# LeggedBot.net
KiCad netlist of a schematic drawn in Altium Designer
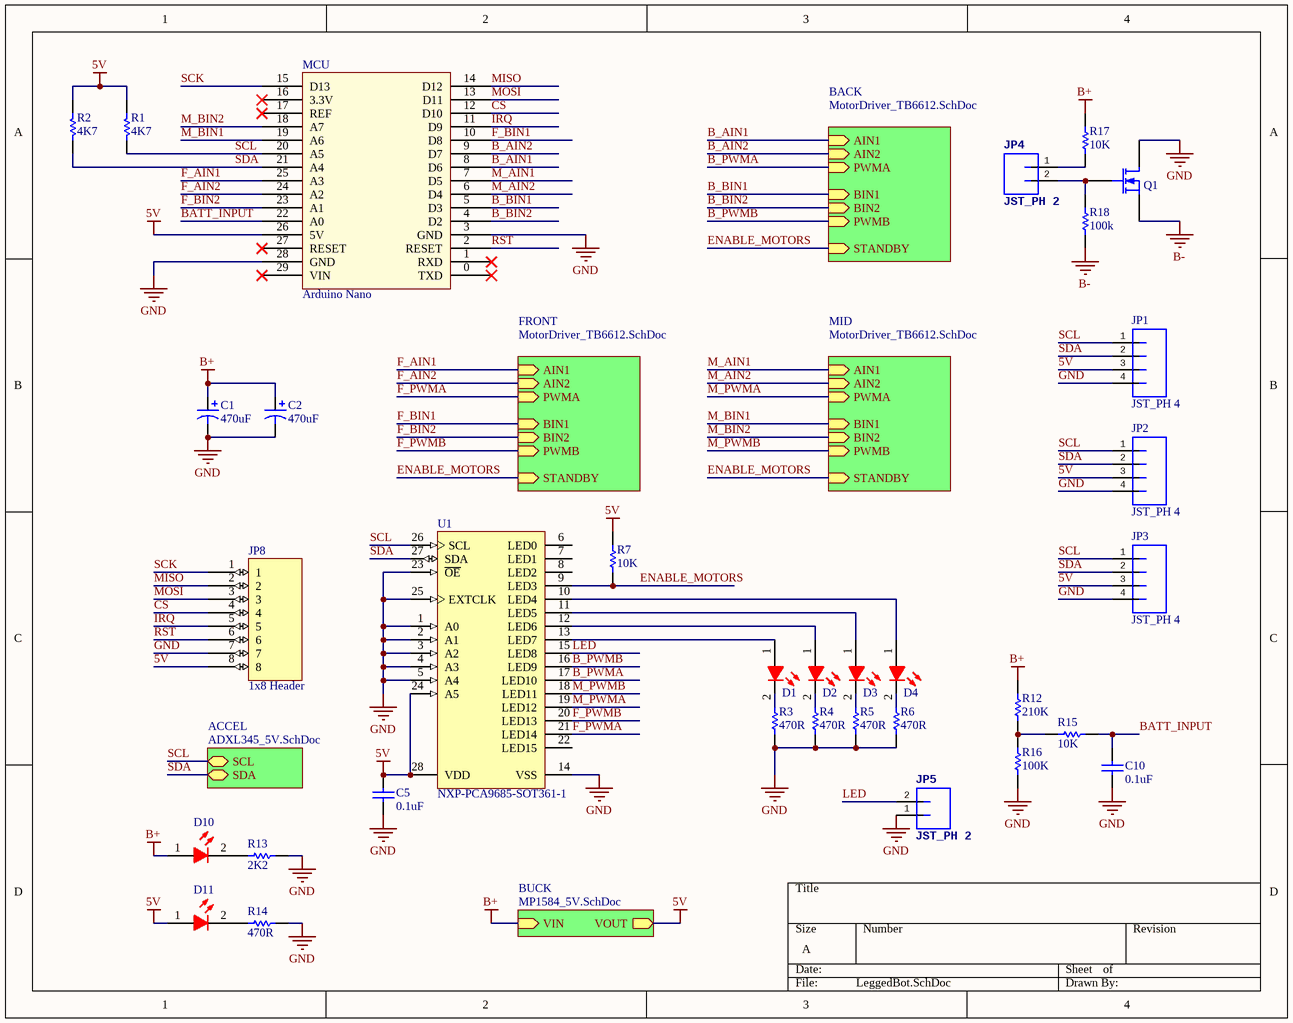
[diagram p0: LeggedBot.SchDoc]

(export (version "E")
  (design (tool "Eeschema 10.0.6"))
  (components
    (comp (ref "C1")
      (value "470uF")
      (footprint "CAP_10mm")
      (description "Generic electrolytic capacitor w/ 10mm diameter and 5mm pitch")
      (libsource (lib "Components") (part "CAP_10MM_GENERIC"))
    )
    (comp (ref "C2")
      (value "470uF")
      (footprint "CAP_10mm")
      (description "Generic electrolytic capacitor w/ 10mm diameter and 5mm pitch")
      (libsource (lib "Components") (part "CAP_10MM_GENERIC"))
    )
    (comp (ref "C5")
      (value "0.1uF")
      (footprint "CAPC0603(1608)100_L")
      (description "CAP 100nF 50V ±5% 0603 (1608 Metric) Thickness 1mm SMD")
      (fields (field (name "TOLERANCE") "Â±5%"))
      (libsource (lib "Altium Content Vault") (part "CMP-1035-02591-1"))
    )
    (comp (ref "C10")
      (value "0.1uF")
      (footprint "CAPC0603(1608)100_L")
      (description "CAP 100nF 50V ±5% 0603 (1608 Metric) Thickness 1mm SMD")
      (fields (field (name "TOLERANCE") "Â±5%"))
      (libsource (lib "Altium Content Vault") (part "CMP-1035-02591-1"))
    )
    (comp (ref "D1")
      (value "TLSU1008A(T04)")
      (footprint "TOSH-0603LED_RED_V")
      (description "LED, Red 0603 (1608) 63mCd")
      (fields (field (name "MANUFACTURER") "Toshiba"))
      (libsource (lib "Altium Content Vault") (part "CMP-0444-00001-1"))
    )
    (comp (ref "D2")
      (value "TLSU1008A(T04)")
      (footprint "TOSH-0603LED_RED_V")
      (description "LED, Red 0603 (1608) 63mCd")
      (fields (field (name "MANUFACTURER") "Toshiba"))
      (libsource (lib "Altium Content Vault") (part "CMP-0444-00001-1"))
    )
    (comp (ref "D3")
      (value "TLSU1008A(T04)")
      (footprint "TOSH-0603LED_RED_V")
      (description "LED, Red 0603 (1608) 63mCd")
      (fields (field (name "MANUFACTURER") "Toshiba"))
      (libsource (lib "Altium Content Vault") (part "CMP-0444-00001-1"))
    )
    (comp (ref "D4")
      (value "TLSU1008A(T04)")
      (footprint "TOSH-0603LED_RED_V")
      (description "LED, Red 0603 (1608) 63mCd")
      (fields (field (name "MANUFACTURER") "Toshiba"))
      (libsource (lib "Altium Content Vault") (part "CMP-0444-00001-1"))
    )
    (comp (ref "D10")
      (value "TLSU1008A(T04)")
      (footprint "TOSH-0603LED_RED_V")
      (description "LED, Red 0603 (1608) 63mCd")
      (fields (field (name "MANUFACTURER") "Toshiba"))
      (libsource (lib "Altium Content Vault") (part "CMP-0444-00001-1"))
    )
    (comp (ref "D11")
      (value "TLSU1008A(T04)")
      (footprint "TOSH-0603LED_RED_V")
      (description "LED, Red 0603 (1608) 63mCd")
      (fields (field (name "MANUFACTURER") "Toshiba"))
      (libsource (lib "Altium Content Vault") (part "CMP-0444-00001-1"))
    )
    (comp (ref "JP1")
      (value "JST_PH 4")
      (footprint "JST-4-PTH-VERT")
      (libsource (lib "Components") (part "JST_PH 4"))
    )
    (comp (ref "JP2")
      (value "JST_PH 4")
      (footprint "JST-4-PTH-VERT")
      (libsource (lib "Components") (part "JST_PH 4"))
    )
    (comp (ref "JP3")
      (value "JST_PH 4")
      (footprint "JST-4-PTH-VERT")
      (libsource (lib "Components") (part "JST_PH 4"))
    )
    (comp (ref "JP4")
      (value "JST_PH 2")
      (footprint "JST-2-PTH-VERT")
      (libsource (lib "Components") (part "JST_PH 2"))
    )
    (comp (ref "JP5")
      (value "JST_PH 2")
      (footprint "JST-2-PTH-VERT")
      (libsource (lib "Components") (part "JST_PH 2"))
    )
    (comp (ref "JP8")
      (value "1x8 Header")
      (footprint "Header 8x1 8.5mm")
      (libsource (lib "Components") (part "1x8 Header"))
    )
    (comp (ref "MCU")
      (value "Arduino Nano")
      (footprint "Arduino Nano")
      (libsource (lib "Components") (part "Arduino Nano"))
    )
    (comp (ref "Q1")
      (value "MOSFET-N")
      (footprint "SOIC127P600X175-8N")
      (description "N-Channel MOSFET")
      (fields (field (name "PUBLISHER") "Altium Limited"))
      (libsource (lib "Components") (part "MOSFET-N"))
    )
    (comp (ref "R1")
      (value "4K7")
      (footprint "RESC0603(1608)_L")
      (description "4K7 0.1W 5% 0603 (1608 Metric)  SMD")
      (fields (field (name "TOLERANCE") "5 %") (field (name "POWER") "0.1 W"))
      (libsource (lib "Altium Content Vault") (part "CMP-1012-00090-1"))
    )
    (comp (ref "R2")
      (value "4K7")
      (footprint "RESC0603(1608)_L")
      (description "4K7 0.1W 5% 0603 (1608 Metric)  SMD")
      (fields (field (name "TOLERANCE") "5 %") (field (name "POWER") "0.1 W"))
      (libsource (lib "Altium Content Vault") (part "CMP-1012-00090-1"))
    )
    (comp (ref "R3")
      (value "470R")
      (footprint "RESC0603(1608)_L")
      (description "470R 0.1W 5% 0603 (1608 Metric)  SMD")
      (fields (field (name "TOLERANCE") "5 %") (field (name "POWER") "0.1 W"))
      (libsource (lib "Altium Content Vault") (part "RES"))
    )
    (comp (ref "R4")
      (value "470R")
      (footprint "RESC0603(1608)_L")
      (description "470R 0.1W 5% 0603 (1608 Metric)  SMD")
      (fields (field (name "TOLERANCE") "5 %") (field (name "POWER") "0.1 W"))
      (libsource (lib "Altium Content Vault") (part "RES"))
    )
    (comp (ref "R5")
      (value "470R")
      (footprint "RESC0603(1608)_L")
      (description "470R 0.1W 5% 0603 (1608 Metric)  SMD")
      (fields (field (name "TOLERANCE") "5 %") (field (name "POWER") "0.1 W"))
      (libsource (lib "Altium Content Vault") (part "CMP-1012-00066-1"))
    )
    (comp (ref "R6")
      (value "470R")
      (footprint "RESC0603(1608)_L")
      (description "470R 0.1W 5% 0603 (1608 Metric)  SMD")
      (fields (field (name "TOLERANCE") "5 %") (field (name "POWER") "0.1 W"))
      (libsource (lib "Altium Content Vault") (part "CMP-1012-00066-1"))
    )
    (comp (ref "R7")
      (value "10K")
      (footprint "RESC0603(1608)_L")
      (description "10K 0.1W 5% 0603 (1608 Metric)  SMD")
      (fields (field (name "TOLERANCE") "5 %") (field (name "POWER") "0.1 W"))
      (libsource (lib "Altium Content Vault") (part "RES"))
    )
    (comp (ref "R12")
      (value "210K")
      (footprint "RESC0603(1608)_L")
      (description "210K 0.1W 1% 0603 (1608 Metric)  SMD")
      (fields (field (name "POWER") "0.1 W") (field (name "TOLERANCE") "1 %"))
      (libsource (lib "Altium Content Vault") (part "CMP-1012-00770-1"))
    )
    (comp (ref "R13")
      (value "2K2")
      (footprint "RESC0603(1608)_L")
      (description "2K2 0.1W 5% 0603 (1608 Metric)  SMD")
      (fields (field (name "POWER") "0.1 W") (field (name "TOLERANCE") "5 %"))
      (libsource (lib "Altium Content Vault") (part "RES"))
    )
    (comp (ref "R14")
      (value "470R")
      (footprint "RESC0603(1608)_L")
      (description "470R 0.1W 5% 0603 (1608 Metric)  SMD")
      (fields (field (name "TOLERANCE") "5 %") (field (name "POWER") "0.1 W"))
      (libsource (lib "Altium Content Vault") (part "RES"))
    )
    (comp (ref "R15")
      (value "10K")
      (footprint "RESC0603(1608)_L")
      (description "10K 0.1W 5% 0603 (1608 Metric)  SMD")
      (fields (field (name "TOLERANCE") "5 %") (field (name "POWER") "0.1 W"))
      (libsource (lib "Altium Content Vault") (part "CMP-1012-00098-1"))
    )
    (comp (ref "R16")
      (value "100K")
      (footprint "RESC0603(1608)_L")
      (description "100K 0.1W 1% 0603 (1608 Metric)  SMD")
      (fields (field (name "POWER") "0.1 W") (field (name "TOLERANCE") "1 %"))
      (libsource (lib "Altium Content Vault") (part "RES"))
    )
    (comp (ref "R17")
      (value "10K")
      (footprint "RESC0603(1608)_L")
      (description "10K 0.1W 5% 0603 (1608 Metric)  SMD")
      (fields (field (name "TOLERANCE") "5 %") (field (name "POWER") "0.1 W"))
      (libsource (lib "Altium Content Vault") (part "CMP-1012-00098-1"))
    )
    (comp (ref "R18")
      (value "100k")
      (footprint "RESC0603(1608)_L")
      (description "100K 0.1W 1% 0603 (1608 Metric)  SMD")
      (fields (field (name "POWER") "0.1 W") (field (name "TOLERANCE") "1 %"))
      (libsource (lib "Altium Content Vault") (part "RES"))
    )
    (comp (ref "U1")
      (value "NXP-PCA9685-SOT361-1")
      (footprint "TSSOP-28")
      (libsource (lib "Components") (part "NXP-PCA9685-SOT361-1"))
    )
  )
  (nets
    (net (code "1") (name "/BATT_INPUT") (class "Default")
      (node (ref "C10") (pin "2") (pinfunction "2_2") (pintype "passive"))
      (node (ref "MCU") (pin "22") (pinfunction "A0_22") (pintype "passive"))
      (node (ref "R15") (pin "1") (pinfunction "1_1") (pintype "passive"))
    )
    (net (code "2") (name "/B_AIN1") (class "Default")
      (node (ref "MCU") (pin "8") (pinfunction "D6_8") (pintype "passive"))
    )
    (net (code "3") (name "/B_AIN2") (class "Default")
      (node (ref "MCU") (pin "9") (pinfunction "D7_9") (pintype "passive"))
    )
    (net (code "4") (name "/B_BIN1") (class "Default")
      (node (ref "MCU") (pin "5") (pinfunction "D3_5") (pintype "passive"))
    )
    (net (code "5") (name "/B_BIN2") (class "Default")
      (node (ref "MCU") (pin "4") (pinfunction "D2_4") (pintype "passive"))
    )
    (net (code "6") (name "/B_PWMA") (class "Default")
      (node (ref "U1") (pin "17") (pinfunction "LED10_17") (pintype "tri_state"))
    )
    (net (code "7") (name "/B_PWMB") (class "Default")
      (node (ref "U1") (pin "16") (pinfunction "LED9_16") (pintype "tri_state"))
    )
    (net (code "8") (name "/CS") (class "Default")
      (node (ref "JP8") (pin "4") (pinfunction "4_4") (pintype "bidirectional"))
      (node (ref "MCU") (pin "12") (pinfunction "D10_12") (pintype "passive"))
    )
    (net (code "9") (name "/ENABLE_MOTORS") (class "Default")
      (node (ref "R7") (pin "1") (pinfunction "1_1") (pintype "passive"))
      (node (ref "U1") (pin "9") (pinfunction "LED3_9") (pintype "tri_state"))
    )
    (net (code "10") (name "/F_AIN1") (class "Default")
      (node (ref "MCU") (pin "25") (pinfunction "A3_25") (pintype "passive"))
    )
    (net (code "11") (name "/F_AIN2") (class "Default")
      (node (ref "MCU") (pin "24") (pinfunction "A2_24") (pintype "passive"))
    )
    (net (code "12") (name "/F_BIN1") (class "Default")
      (node (ref "MCU") (pin "10") (pinfunction "D8_10") (pintype "passive"))
    )
    (net (code "13") (name "/F_BIN2") (class "Default")
      (node (ref "MCU") (pin "23") (pinfunction "A1_23") (pintype "passive"))
    )
    (net (code "14") (name "/F_PWMA") (class "Default")
      (node (ref "U1") (pin "21") (pinfunction "LED14_21") (pintype "tri_state"))
    )
    (net (code "15") (name "/F_PWMB") (class "Default")
      (node (ref "U1") (pin "20") (pinfunction "LED13_20") (pintype "tri_state"))
    )
    (net (code "16") (name "/IRQ") (class "Default")
      (node (ref "JP8") (pin "5") (pinfunction "5_5") (pintype "bidirectional"))
      (node (ref "MCU") (pin "11") (pinfunction "D9_11") (pintype "passive"))
    )
    (net (code "17") (name "/LED") (class "Default")
      (node (ref "JP5") (pin "2") (pinfunction "2_2") (pintype "passive"))
      (node (ref "U1") (pin "15") (pinfunction "LED8_15") (pintype "tri_state"))
    )
    (net (code "18") (name "/MISO") (class "Default")
      (node (ref "JP8") (pin "2") (pinfunction "2_2") (pintype "bidirectional"))
      (node (ref "MCU") (pin "14") (pinfunction "D12_14") (pintype "passive"))
    )
    (net (code "19") (name "/MOSI") (class "Default")
      (node (ref "JP8") (pin "3") (pinfunction "3_3") (pintype "bidirectional"))
      (node (ref "MCU") (pin "13") (pinfunction "D11_13") (pintype "passive"))
    )
    (net (code "20") (name "/M_AIN1") (class "Default")
      (node (ref "MCU") (pin "7") (pinfunction "D5_7") (pintype "passive"))
    )
    (net (code "21") (name "/M_AIN2") (class "Default")
      (node (ref "MCU") (pin "6") (pinfunction "D4_6") (pintype "passive"))
    )
    (net (code "22") (name "/M_BIN1") (class "Default")
      (node (ref "MCU") (pin "19") (pinfunction "A6_19") (pintype "passive"))
    )
    (net (code "23") (name "/M_BIN2") (class "Default")
      (node (ref "MCU") (pin "18") (pinfunction "A7_18") (pintype "passive"))
    )
    (net (code "24") (name "/M_PWMA") (class "Default")
      (node (ref "U1") (pin "19") (pinfunction "LED12_19") (pintype "tri_state"))
    )
    (net (code "25") (name "/M_PWMB") (class "Default")
      (node (ref "U1") (pin "18") (pinfunction "LED11_18") (pintype "tri_state"))
    )
    (net (code "26") (name "/RST") (class "Default")
      (node (ref "JP8") (pin "6") (pinfunction "6_6") (pintype "bidirectional"))
      (node (ref "MCU") (pin "2") (pinfunction "RESET_2") (pintype "passive"))
    )
    (net (code "27") (name "/SCK") (class "Default")
      (node (ref "JP8") (pin "1") (pinfunction "1_1") (pintype "bidirectional"))
      (node (ref "MCU") (pin "15") (pinfunction "D13_15") (pintype "passive"))
    )
    (net (code "28") (name "/SCL") (class "Default")
      (node (ref "JP1") (pin "1") (pinfunction "1_1") (pintype "passive"))
      (node (ref "JP2") (pin "1") (pinfunction "1_1") (pintype "passive"))
      (node (ref "JP3") (pin "1") (pinfunction "1_1") (pintype "passive"))
      (node (ref "MCU") (pin "20") (pinfunction "A5_20") (pintype "passive"))
      (node (ref "R1") (pin "1") (pinfunction "1_1") (pintype "passive"))
      (node (ref "U1") (pin "26") (pinfunction "SCL_26") (pintype "input"))
    )
    (net (code "29") (name "/SDA") (class "Default")
      (node (ref "JP1") (pin "2") (pinfunction "2_2") (pintype "passive"))
      (node (ref "JP2") (pin "2") (pinfunction "2_2") (pintype "passive"))
      (node (ref "JP3") (pin "2") (pinfunction "2_2") (pintype "passive"))
      (node (ref "MCU") (pin "21") (pinfunction "A4_21") (pintype "passive"))
      (node (ref "R2") (pin "1") (pinfunction "1_1") (pintype "passive"))
      (node (ref "U1") (pin "27") (pinfunction "SDA_27") (pintype "bidirectional"))
    )
    (net (code "30") (name "5V") (class "Default")
      (node (ref "C5") (pin "2") (pinfunction "2_2") (pintype "passive"))
      (node (ref "D11") (pin "1") (pinfunction "A_1") (pintype "passive"))
      (node (ref "JP1") (pin "3") (pinfunction "3_3") (pintype "passive"))
      (node (ref "JP2") (pin "3") (pinfunction "3_3") (pintype "passive"))
      (node (ref "JP3") (pin "3") (pinfunction "3_3") (pintype "passive"))
      (node (ref "JP8") (pin "8") (pinfunction "8_8") (pintype "bidirectional"))
      (node (ref "MCU") (pin "26") (pinfunction "5V_26") (pintype "passive"))
      (node (ref "R1") (pin "2") (pinfunction "2_2") (pintype "passive"))
      (node (ref "R2") (pin "2") (pinfunction "2_2") (pintype "passive"))
      (node (ref "R7") (pin "2") (pinfunction "2_2") (pintype "passive"))
      (node (ref "U1") (pin "24") (pinfunction "A5_24") (pintype "input"))
      (node (ref "U1") (pin "28") (pinfunction "VDD_28") (pintype "power_in"))
    )
    (net (code "31") (name "B+") (class "Default")
      (node (ref "C1") (pin "0") (pinfunction "0_0") (pintype "passive"))
      (node (ref "C2") (pin "0") (pinfunction "0_0") (pintype "passive"))
      (node (ref "D10") (pin "1") (pinfunction "A_1") (pintype "passive"))
      (node (ref "R12") (pin "2") (pinfunction "2_2") (pintype "passive"))
      (node (ref "R17") (pin "2") (pinfunction "2_2") (pintype "passive"))
    )
    (net (code "32") (name "B-") (class "Default")
      (node (ref "Q1") (pin "3") (pinfunction "S_3") (pintype "passive"))
      (node (ref "R18") (pin "1") (pinfunction "1_1") (pintype "passive"))
    )
    (net (code "33") (name "GND") (class "Default")
      (node (ref "C1") (pin "1") (pinfunction "1_1") (pintype "passive"))
      (node (ref "C10") (pin "1") (pinfunction "1_1") (pintype "passive"))
      (node (ref "C2") (pin "1") (pinfunction "1_1") (pintype "passive"))
      (node (ref "C5") (pin "1") (pinfunction "1_1") (pintype "passive"))
      (node (ref "JP1") (pin "4") (pinfunction "4_4") (pintype "passive"))
      (node (ref "JP2") (pin "4") (pinfunction "4_4") (pintype "passive"))
      (node (ref "JP3") (pin "4") (pinfunction "4_4") (pintype "passive"))
      (node (ref "JP5") (pin "1") (pinfunction "1_1") (pintype "passive"))
      (node (ref "JP8") (pin "7") (pinfunction "7_7") (pintype "bidirectional"))
      (node (ref "MCU") (pin "28") (pinfunction "GND_28") (pintype "passive"))
      (node (ref "MCU") (pin "3") (pinfunction "GND_3") (pintype "passive"))
      (node (ref "Q1") (pin "2") (pinfunction "D_2") (pintype "passive"))
      (node (ref "R13") (pin "2") (pinfunction "2_2") (pintype "passive"))
      (node (ref "R14") (pin "1") (pinfunction "1_1") (pintype "passive"))
      (node (ref "R16") (pin "1") (pinfunction "1_1") (pintype "passive"))
      (node (ref "R3") (pin "1") (pinfunction "1_1") (pintype "passive"))
      (node (ref "R4") (pin "1") (pinfunction "1_1") (pintype "passive"))
      (node (ref "R5") (pin "1") (pinfunction "1_1") (pintype "passive"))
      (node (ref "R6") (pin "1") (pinfunction "1_1") (pintype "passive"))
      (node (ref "U1") (pin "1") (pinfunction "A0_1") (pintype "input"))
      (node (ref "U1") (pin "14") (pinfunction "VSS_14") (pintype "power_in"))
      (node (ref "U1") (pin "2") (pinfunction "A1_2") (pintype "input"))
      (node (ref "U1") (pin "23") (pinfunction "~{OE}_23") (pintype "input"))
      (node (ref "U1") (pin "25") (pinfunction "EXTCLK_25") (pintype "input"))
      (node (ref "U1") (pin "3") (pinfunction "A2_3") (pintype "input"))
      (node (ref "U1") (pin "4") (pinfunction "A3_4") (pintype "input"))
      (node (ref "U1") (pin "5") (pinfunction "A4_5") (pintype "input"))
    )
    (net (code "34") (name "Net-(D1-A)") (class "Default")
      (node (ref "D1") (pin "1") (pinfunction "A_1") (pintype "passive"))
      (node (ref "U1") (pin "13") (pinfunction "LED7_13") (pintype "tri_state"))
    )
    (net (code "35") (name "Net-(D1-K)") (class "Default")
      (node (ref "D1") (pin "2") (pinfunction "K_2") (pintype "passive"))
      (node (ref "R3") (pin "2") (pinfunction "2_2") (pintype "passive"))
    )
    (net (code "36") (name "Net-(D2-A)") (class "Default")
      (node (ref "D2") (pin "1") (pinfunction "A_1") (pintype "passive"))
      (node (ref "U1") (pin "12") (pinfunction "LED6_12") (pintype "tri_state"))
    )
    (net (code "37") (name "Net-(D2-K)") (class "Default")
      (node (ref "D2") (pin "2") (pinfunction "K_2") (pintype "passive"))
      (node (ref "R4") (pin "2") (pinfunction "2_2") (pintype "passive"))
    )
    (net (code "38") (name "Net-(D3-A)") (class "Default")
      (node (ref "D3") (pin "1") (pinfunction "A_1") (pintype "passive"))
      (node (ref "U1") (pin "11") (pinfunction "LED5_11") (pintype "tri_state"))
    )
    (net (code "39") (name "Net-(D3-K)") (class "Default")
      (node (ref "D3") (pin "2") (pinfunction "K_2") (pintype "passive"))
      (node (ref "R5") (pin "2") (pinfunction "2_2") (pintype "passive"))
    )
    (net (code "40") (name "Net-(D4-A)") (class "Default")
      (node (ref "D4") (pin "1") (pinfunction "A_1") (pintype "passive"))
      (node (ref "U1") (pin "10") (pinfunction "LED4_10") (pintype "tri_state"))
    )
    (net (code "41") (name "Net-(D4-K)") (class "Default")
      (node (ref "D4") (pin "2") (pinfunction "K_2") (pintype "passive"))
      (node (ref "R6") (pin "2") (pinfunction "2_2") (pintype "passive"))
    )
    (net (code "42") (name "Net-(D10-K)") (class "Default")
      (node (ref "D10") (pin "2") (pinfunction "K_2") (pintype "passive"))
      (node (ref "R13") (pin "1") (pinfunction "1_1") (pintype "passive"))
    )
    (net (code "43") (name "Net-(D11-K)") (class "Default")
      (node (ref "D11") (pin "2") (pinfunction "K_2") (pintype "passive"))
      (node (ref "R14") (pin "2") (pinfunction "2_2") (pintype "passive"))
    )
    (net (code "44") (name "Net-(JP4-Pad1)") (class "Default")
      (node (ref "JP4") (pin "1") (pinfunction "1_1") (pintype "passive"))
      (node (ref "R17") (pin "1") (pinfunction "1_1") (pintype "passive"))
    )
    (net (code "45") (name "Net-(Q1-G)") (class "Default")
      (node (ref "JP4") (pin "2") (pinfunction "2_2") (pintype "passive"))
      (node (ref "Q1") (pin "1") (pinfunction "G_1") (pintype "passive"))
      (node (ref "R18") (pin "2") (pinfunction "2_2") (pintype "passive"))
    )
    (net (code "46") (name "Net-(R12-Pad1)") (class "Default")
      (node (ref "R12") (pin "1") (pinfunction "1_1") (pintype "passive"))
      (node (ref "R15") (pin "2") (pinfunction "2_2") (pintype "passive"))
      (node (ref "R16") (pin "2") (pinfunction "2_2") (pintype "passive"))
    )
    (net (code "47") (name "unconnected-(MCU-3.3V-Pad16)") (class "Default")
      (node (ref "MCU") (pin "16") (pinfunction "3.3V_16") (pintype "passive+no_connect"))
    )
    (net (code "48") (name "unconnected-(MCU-REF-Pad17)") (class "Default")
      (node (ref "MCU") (pin "17") (pinfunction "REF_17") (pintype "passive+no_connect"))
    )
    (net (code "49") (name "unconnected-(MCU-RESET-Pad27)") (class "Default")
      (node (ref "MCU") (pin "27") (pinfunction "RESET_27") (pintype "passive+no_connect"))
    )
    (net (code "50") (name "unconnected-(MCU-RXD-Pad1)") (class "Default")
      (node (ref "MCU") (pin "1") (pinfunction "RXD_1") (pintype "passive+no_connect"))
    )
    (net (code "51") (name "unconnected-(MCU-TXD-Pad0)") (class "Default")
      (node (ref "MCU") (pin "0") (pinfunction "TXD_0") (pintype "passive+no_connect"))
    )
    (net (code "52") (name "unconnected-(MCU-VIN-Pad29)") (class "Default")
      (node (ref "MCU") (pin "29") (pinfunction "VIN_29") (pintype "passive+no_connect"))
    )
    (net (code "53") (name "unconnected-(U1-LED0-Pad6)") (class "Default")
      (node (ref "U1") (pin "6") (pinfunction "LED0_6") (pintype "tri_state"))
    )
    (net (code "54") (name "unconnected-(U1-LED1-Pad7)") (class "Default")
      (node (ref "U1") (pin "7") (pinfunction "LED1_7") (pintype "tri_state"))
    )
    (net (code "55") (name "unconnected-(U1-LED2-Pad8)") (class "Default")
      (node (ref "U1") (pin "8") (pinfunction "LED2_8") (pintype "tri_state"))
    )
    (net (code "56") (name "unconnected-(U1-LED15-Pad22)") (class "Default")
      (node (ref "U1") (pin "22") (pinfunction "LED15_22") (pintype "tri_state"))
    )
  )
)
